# central_sensores.net
KiCad netlist of a schematic drawn in EAGLE
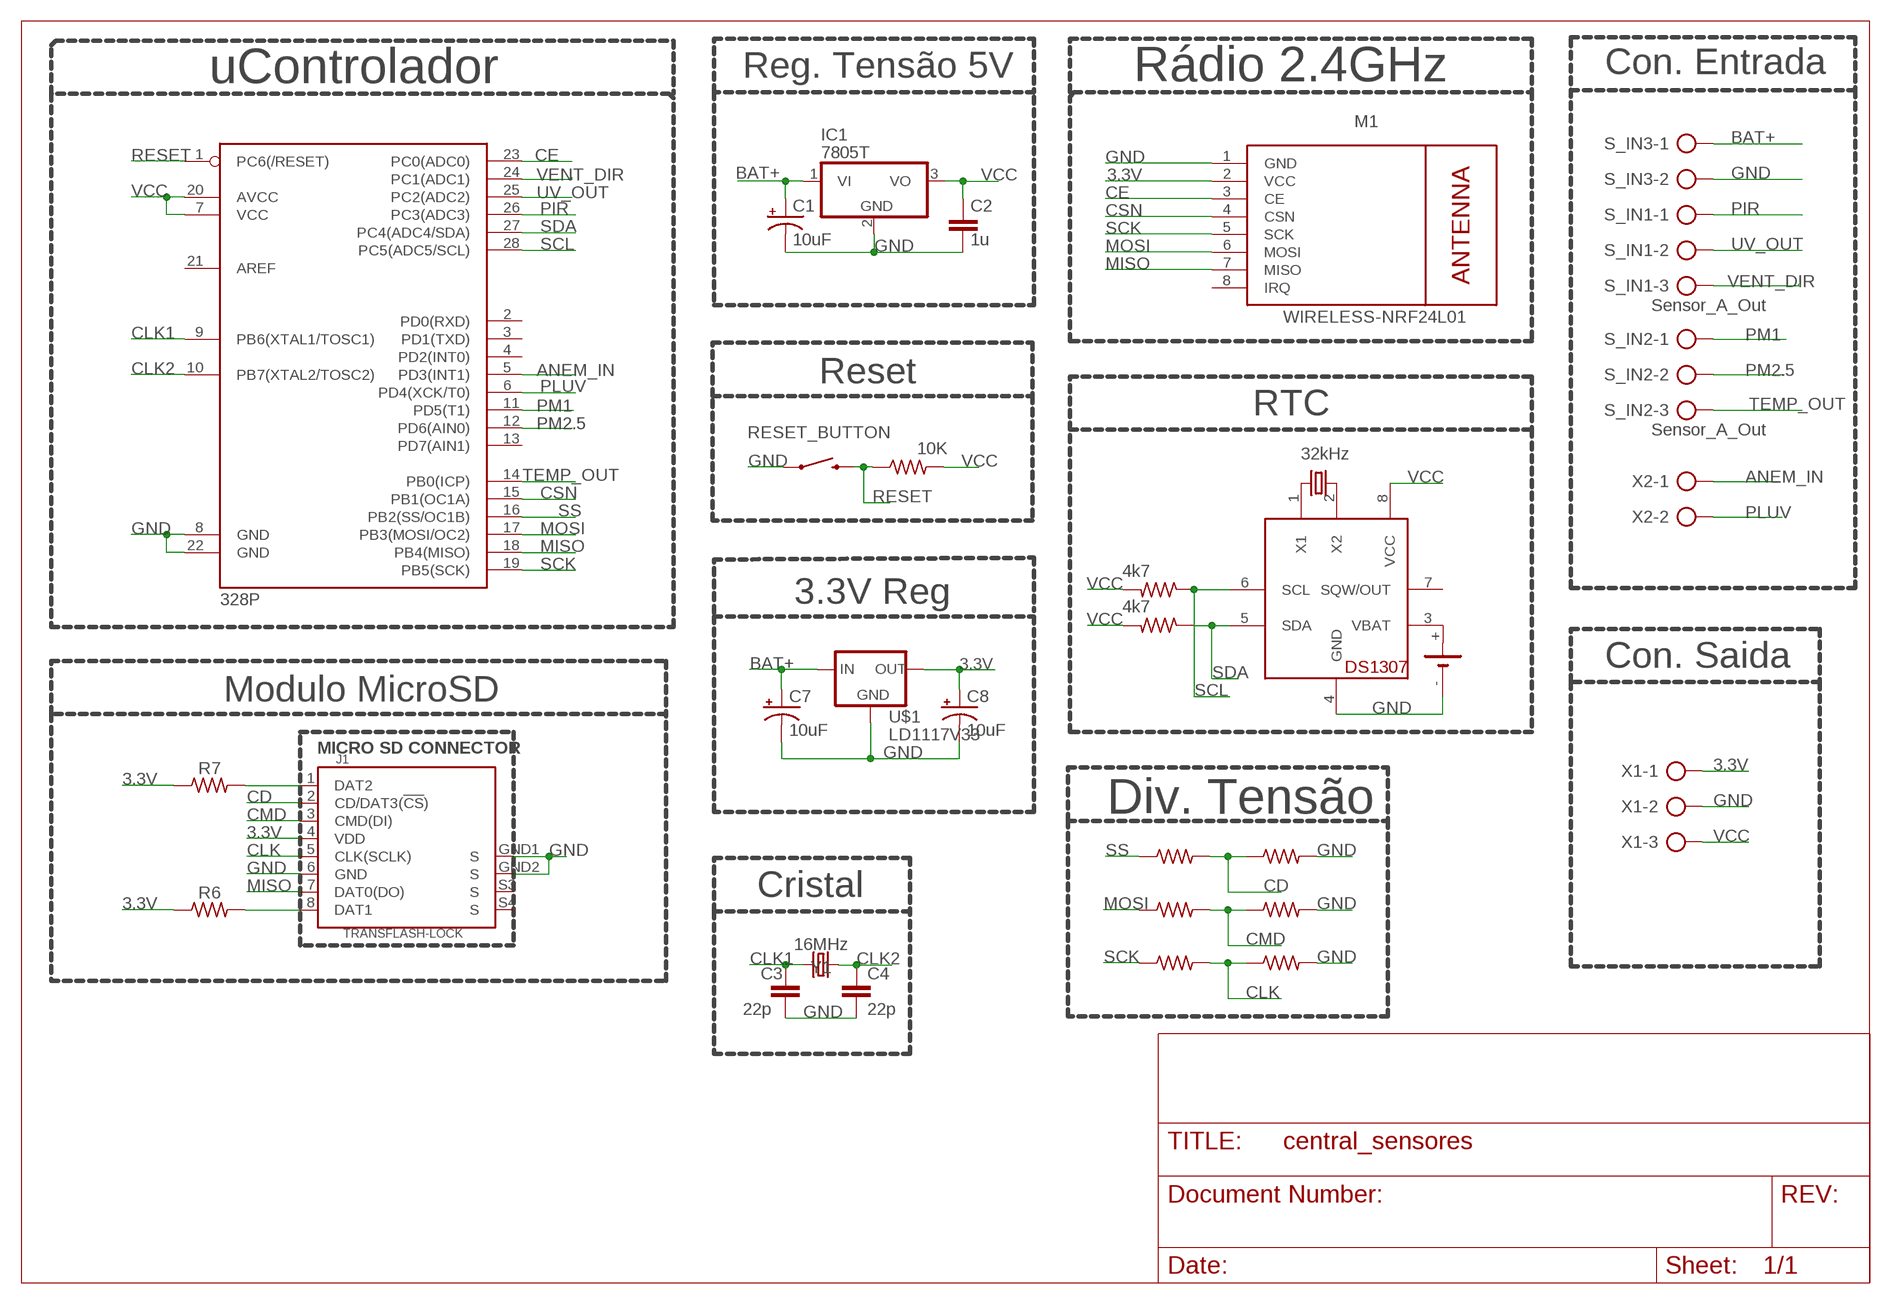
[diagram p0: schematic, sheet 1]

(export (version "E")
  (design (tool "Eeschema 10.0.6"))
  (components
    (comp (ref "C1")
      (value "10uF")
      (footprint "eagle-import:CPOL-RADIAL-2.5MM-5MM")
      (libsource (lib "eagle-import") (part "10UF-POLAR-RADIAL-2.5MM-25V-20%"))
    )
    (comp (ref "C2")
      (value "1u")
      (footprint "eagle-import:C025-024X044")
      (libsource (lib "eagle-import") (part "C-EU025-024X044"))
    )
    (comp (ref "C3")
      (value "22p")
      (footprint "eagle-import:C2.5-3")
      (libsource (lib "eagle-import") (part "C2,5-3"))
    )
    (comp (ref "C4")
      (value "22p")
      (footprint "eagle-import:C2.5-3")
      (libsource (lib "eagle-import") (part "C2,5-3"))
    )
    (comp (ref "C7")
      (value "10uF")
      (footprint "eagle-import:CPOL-RADIAL-2.5MM-5MM")
      (libsource (lib "eagle-import") (part "10UF-POLAR-RADIAL-2.5MM-25V-20%"))
    )
    (comp (ref "C8")
      (value "10uF")
      (footprint "eagle-import:CPOL-RADIAL-2.5MM-5MM")
      (libsource (lib "eagle-import") (part "10UF-POLAR-RADIAL-2.5MM-25V-20%"))
    )
    (comp (ref "G2")
      (value "CH291-1220LF")
      (footprint "eagle-import:CH291-1220LF")
      (libsource (lib "eagle-import") (part "CH291-1220LF"))
    )
    (comp (ref "IC1")
      (value "7805T")
      (footprint "eagle-import:TO220H")
      (libsource (lib "eagle-import") (part "78T05"))
    )
    (comp (ref "IC2")
      (value "DS1307")
      (footprint "eagle-import:DIL08")
      (libsource (lib "eagle-import") (part "DS1307"))
    )
    (comp (ref "J1")
      (value "TRANSFLASH-LOCK")
      (footprint "eagle-import:TRANSFLASH-LOCK-SOCK")
      (libsource (lib "eagle-import") (part "TRANSFLASH-LOCK"))
    )
    (comp (ref "M1")
      (value "WIRELESS-NRF24L01")
      (footprint "eagle-import:WIRELESS-NRF24L01")
      (libsource (lib "eagle-import") (part "WIRELESS-NRF24L01"))
    )
    (comp (ref "R1")
      (value "10K")
      (footprint "eagle-import:0204_7")
      (libsource (lib "eagle-import") (part "R-US_0204/7"))
    )
    (comp (ref "R2")
      (value "R-US_0204/7")
      (footprint "eagle-import:0204_7")
      (libsource (lib "eagle-import") (part "resistor_R-US_0204/7"))
    )
    (comp (ref "R3")
      (value "R-US_0204/7")
      (footprint "eagle-import:0204_7")
      (libsource (lib "eagle-import") (part "resistor_R-US_0204/7"))
    )
    (comp (ref "R4")
      (value "4k7")
      (footprint "eagle-import:0204_7")
      (libsource (lib "eagle-import") (part "R-US_0204/7"))
    )
    (comp (ref "R5")
      (value "4k7")
      (footprint "eagle-import:0204_7")
      (libsource (lib "eagle-import") (part "R-US_0204/7"))
    )
    (comp (ref "R6")
      (value "100k")
      (footprint "eagle-import:0204_7")
      (libsource (lib "eagle-import") (part "resistor_R-US_0204/7"))
    )
    (comp (ref "R7")
      (value "100k")
      (footprint "eagle-import:0204_7")
      (libsource (lib "eagle-import") (part "resistor_R-US_0204/7"))
    )
    (comp (ref "R8")
      (value "R-US_0204/7")
      (footprint "eagle-import:0204_7")
      (libsource (lib "eagle-import") (part "resistor_R-US_0204/7"))
    )
    (comp (ref "R9")
      (value "R-US_0204/7")
      (footprint "eagle-import:0204_7")
      (libsource (lib "eagle-import") (part "resistor_R-US_0204/7"))
    )
    (comp (ref "R10")
      (value "R-US_0204/7")
      (footprint "eagle-import:0204_7")
      (libsource (lib "eagle-import") (part "resistor_R-US_0204/7"))
    )
    (comp (ref "R11")
      (value "R-US_0204/7")
      (footprint "eagle-import:0204_7")
      (libsource (lib "eagle-import") (part "resistor_R-US_0204/7"))
    )
    (comp (ref "RESET_BUTTON")
      (value "MOMENTARY-SWITCH-SPST-PTH-6.0MM")
      (footprint "eagle-import:TACTILE_SWITCH_PTH_6.0MM")
      (libsource (lib "eagle-import") (part "MOMENTARY-SWITCH-SPST-PTH-6.0MM"))
    )
    (comp (ref "S_IN1")
      (value "Sensor_A_Out")
      (footprint "eagle-import:AK500_3-H")
      (libsource (lib "eagle-import") (part "AK500/3-H"))
    )
    (comp (ref "S_IN2")
      (value "Sensor_A_Out")
      (footprint "eagle-import:AK500_3-H")
      (libsource (lib "eagle-import") (part "AK500/3-H"))
    )
    (comp (ref "S_IN3")
      (value "Sensor_A_Out")
      (footprint "eagle-import:AK500_2-H")
      (libsource (lib "eagle-import") (part "AK500/2-H"))
    )
    (comp (ref "U$1")
      (value "LD1117V33")
      (footprint "eagle-import:LD1117V33")
      (libsource (lib "eagle-import") (part "LD1117V33"))
    )
    (comp (ref "U1")
      (value "328P")
      (footprint "eagle-import:DIP28")
      (libsource (lib "eagle-import") (part "ATMEGA328P_PDIP"))
    )
    (comp (ref "X1")
      (value "AK500/3-H")
      (footprint "eagle-import:AK500_3-H")
      (libsource (lib "eagle-import") (part "AK500/3-H"))
    )
    (comp (ref "X2")
      (value "AK500/2-H")
      (footprint "eagle-import:AK500_2-H")
      (libsource (lib "eagle-import") (part "AK500/2-H"))
    )
    (comp (ref "Y1")
      (value "16MHz")
      (footprint "eagle-import:HC49US")
      (libsource (lib "eagle-import") (part "CRYSTAL-16MHZPTH-HC49US"))
    )
    (comp (ref "Y2")
      (value "32kHz")
      (footprint "eagle-import:TC38H")
      (libsource (lib "eagle-import") (part "CRYSTALTC38H"))
    )
  )
  (nets
    (net (code "1") (name "/3.3V") (class "Default")
      (node (ref "C8") (pin "1") (pinfunction "+_1") (pintype "passive"))
      (node (ref "J1") (pin "4") (pinfunction "VDD_4") (pintype "power_in"))
      (node (ref "M1") (pin "2") (pinfunction "VCC_2") (pintype "power_in"))
      (node (ref "R6") (pin "1") (pinfunction "1_1") (pintype "passive"))
      (node (ref "R7") (pin "1") (pinfunction "1_1") (pintype "passive"))
      (node (ref "U$1") (pin "OUT") (pinfunction "OUT_OUT") (pintype "output"))
      (node (ref "X1") (pin "1") (pinfunction "KL_1") (pintype "passive"))
    )
    (net (code "2") (name "/ANEM_IN") (class "Default")
      (node (ref "U1") (pin "5") (pinfunction "PD3(INT1)_5") (pintype "bidirectional"))
      (node (ref "X2") (pin "1") (pinfunction "KL_1") (pintype "passive"))
    )
    (net (code "3") (name "/BAT+") (class "Default")
      (node (ref "C1") (pin "1") (pinfunction "+_1") (pintype "passive"))
      (node (ref "C7") (pin "1") (pinfunction "+_1") (pintype "passive"))
      (node (ref "IC1") (pin "1") (pinfunction "VI_1") (pintype "input"))
      (node (ref "S_IN3") (pin "1") (pinfunction "KL_1") (pintype "passive"))
      (node (ref "U$1") (pin "IN") (pinfunction "IN_IN") (pintype "input"))
    )
    (net (code "4") (name "/CD") (class "Default")
      (node (ref "J1") (pin "2") (pinfunction "CD/DAT3(~{CS})_2") (pintype "bidirectional"))
      (node (ref "R2") (pin "2") (pinfunction "2_2") (pintype "passive"))
      (node (ref "R3") (pin "1") (pinfunction "1_1") (pintype "passive"))
    )
    (net (code "5") (name "/CE") (class "Default")
      (node (ref "M1") (pin "3") (pinfunction "CE_3") (pintype "bidirectional"))
      (node (ref "U1") (pin "23") (pinfunction "PC0(ADC0)_23") (pintype "bidirectional"))
    )
    (net (code "6") (name "/CLK") (class "Default")
      (node (ref "J1") (pin "5") (pinfunction "CLK(SCLK)_5") (pintype "bidirectional"))
      (node (ref "R10") (pin "2") (pinfunction "2_2") (pintype "passive"))
      (node (ref "R11") (pin "1") (pinfunction "1_1") (pintype "passive"))
    )
    (net (code "7") (name "/CLK1") (class "Default")
      (node (ref "C3") (pin "1") (pinfunction "1_1") (pintype "passive"))
      (node (ref "U1") (pin "9") (pinfunction "PB6(XTAL1/TOSC1)_9") (pintype "bidirectional"))
      (node (ref "Y1") (pin "2") (pinfunction "2_2") (pintype "passive"))
    )
    (net (code "8") (name "/CLK2") (class "Default")
      (node (ref "C4") (pin "1") (pinfunction "1_1") (pintype "passive"))
      (node (ref "U1") (pin "10") (pinfunction "PB7(XTAL2/TOSC2)_10") (pintype "bidirectional"))
      (node (ref "Y1") (pin "1") (pinfunction "1_1") (pintype "passive"))
    )
    (net (code "9") (name "/CMD") (class "Default")
      (node (ref "J1") (pin "3") (pinfunction "CMD(DI)_3") (pintype "bidirectional"))
      (node (ref "R8") (pin "2") (pinfunction "2_2") (pintype "passive"))
      (node (ref "R9") (pin "1") (pinfunction "1_1") (pintype "passive"))
    )
    (net (code "10") (name "/CSN") (class "Default")
      (node (ref "M1") (pin "4") (pinfunction "CSN_4") (pintype "bidirectional"))
      (node (ref "U1") (pin "15") (pinfunction "PB1(OC1A)_15") (pintype "bidirectional"))
    )
    (net (code "11") (name "/GND") (class "Default")
      (node (ref "C1") (pin "2") (pinfunction "-_2") (pintype "passive"))
      (node (ref "C2") (pin "2") (pinfunction "2_2") (pintype "passive"))
      (node (ref "C3") (pin "2") (pinfunction "2_2") (pintype "passive"))
      (node (ref "C4") (pin "2") (pinfunction "2_2") (pintype "passive"))
      (node (ref "C7") (pin "2") (pinfunction "-_2") (pintype "passive"))
      (node (ref "C8") (pin "2") (pinfunction "-_2") (pintype "passive"))
      (node (ref "G2") (pin "-") (pinfunction "-_-") (pintype "passive"))
      (node (ref "IC1") (pin "2") (pinfunction "GND_2") (pintype "passive"))
      (node (ref "IC2") (pin "4") (pinfunction "GND_4") (pintype "power_in"))
      (node (ref "J1") (pin "6") (pinfunction "GND_6") (pintype "power_in"))
      (node (ref "J1") (pin "GND1") (pinfunction "S_GND1") (pintype "passive"))
      (node (ref "J1") (pin "GND2") (pinfunction "S_GND2") (pintype "passive"))
      (node (ref "M1") (pin "1") (pinfunction "GND_1") (pintype "power_in"))
      (node (ref "R11") (pin "2") (pinfunction "2_2") (pintype "passive"))
      (node (ref "R3") (pin "2") (pinfunction "2_2") (pintype "passive"))
      (node (ref "R9") (pin "2") (pinfunction "2_2") (pintype "passive"))
      (node (ref "RESET_BUTTON") (pin "1") (pinfunction "1_1") (pintype "passive"))
      (node (ref "S_IN3") (pin "2") (pinfunction "KL_2") (pintype "passive"))
      (node (ref "U$1") (pin "GND") (pinfunction "GND_GND") (pintype "input"))
      (node (ref "U1") (pin "22") (pinfunction "GND_22") (pintype "bidirectional"))
      (node (ref "U1") (pin "8") (pinfunction "GND_8") (pintype "bidirectional"))
      (node (ref "X1") (pin "2") (pinfunction "KL_2") (pintype "passive"))
    )
    (net (code "12") (name "/MISO") (class "Default")
      (node (ref "J1") (pin "7") (pinfunction "DAT0(DO)_7") (pintype "bidirectional"))
      (node (ref "M1") (pin "7") (pinfunction "MISO_7") (pintype "bidirectional"))
      (node (ref "U1") (pin "18") (pinfunction "PB4(MISO)_18") (pintype "bidirectional"))
    )
    (net (code "13") (name "/MOSI") (class "Default")
      (node (ref "M1") (pin "6") (pinfunction "MOSI_6") (pintype "bidirectional"))
      (node (ref "R8") (pin "1") (pinfunction "1_1") (pintype "passive"))
      (node (ref "U1") (pin "17") (pinfunction "PB3(MOSI/OC2)_17") (pintype "bidirectional"))
    )
    (net (code "14") (name "/PIR") (class "Default")
      (node (ref "S_IN1") (pin "1") (pinfunction "KL_1") (pintype "passive"))
      (node (ref "U1") (pin "26") (pinfunction "PC3(ADC3)_26") (pintype "bidirectional"))
    )
    (net (code "15") (name "/PLUV") (class "Default")
      (node (ref "U1") (pin "6") (pinfunction "PD4(XCK/T0)_6") (pintype "bidirectional"))
      (node (ref "X2") (pin "2") (pinfunction "KL_2") (pintype "passive"))
    )
    (net (code "16") (name "/PM1") (class "Default")
      (node (ref "S_IN2") (pin "1") (pinfunction "KL_1") (pintype "passive"))
      (node (ref "U1") (pin "11") (pinfunction "PD5(T1)_11") (pintype "bidirectional"))
    )
    (net (code "17") (name "/PM2.5") (class "Default")
      (node (ref "S_IN2") (pin "2") (pinfunction "KL_2") (pintype "passive"))
      (node (ref "U1") (pin "12") (pinfunction "PD6(AIN0)_12") (pintype "bidirectional"))
    )
    (net (code "18") (name "/RESET") (class "Default")
      (node (ref "R1") (pin "1") (pinfunction "1_1") (pintype "passive"))
      (node (ref "RESET_BUTTON") (pin "3") (pinfunction "2_3") (pintype "passive"))
      (node (ref "U1") (pin "1") (pinfunction "PC6(/RESET)_1") (pintype "bidirectional"))
    )
    (net (code "19") (name "/SCK") (class "Default")
      (node (ref "M1") (pin "5") (pinfunction "SCK_5") (pintype "bidirectional"))
      (node (ref "R10") (pin "1") (pinfunction "1_1") (pintype "passive"))
      (node (ref "U1") (pin "19") (pinfunction "PB5(SCK)_19") (pintype "bidirectional"))
    )
    (net (code "20") (name "/SCL") (class "Default")
      (node (ref "IC2") (pin "6") (pinfunction "SCL_6") (pintype "bidirectional"))
      (node (ref "R4") (pin "1") (pinfunction "1_1") (pintype "passive"))
      (node (ref "U1") (pin "28") (pinfunction "PC5(ADC5/SCL)_28") (pintype "bidirectional"))
    )
    (net (code "21") (name "/SDA") (class "Default")
      (node (ref "IC2") (pin "5") (pinfunction "SDA_5") (pintype "bidirectional"))
      (node (ref "R5") (pin "1") (pinfunction "1_1") (pintype "passive"))
      (node (ref "U1") (pin "27") (pinfunction "PC4(ADC4/SDA)_27") (pintype "bidirectional"))
    )
    (net (code "22") (name "/SS") (class "Default")
      (node (ref "R2") (pin "1") (pinfunction "1_1") (pintype "passive"))
      (node (ref "U1") (pin "16") (pinfunction "PB2(SS/OC1B)_16") (pintype "bidirectional"))
    )
    (net (code "23") (name "/TEMP_OUT") (class "Default")
      (node (ref "S_IN2") (pin "3") (pinfunction "KL_3") (pintype "passive"))
      (node (ref "U1") (pin "14") (pinfunction "PB0(ICP)_14") (pintype "bidirectional"))
    )
    (net (code "24") (name "/UV_OUT") (class "Default")
      (node (ref "S_IN1") (pin "2") (pinfunction "KL_2") (pintype "passive"))
      (node (ref "U1") (pin "25") (pinfunction "PC2(ADC2)_25") (pintype "bidirectional"))
    )
    (net (code "25") (name "/VCC") (class "Default")
      (node (ref "C2") (pin "1") (pinfunction "1_1") (pintype "passive"))
      (node (ref "IC1") (pin "3") (pinfunction "VO_3") (pintype "passive"))
      (node (ref "IC2") (pin "8") (pinfunction "VCC_8") (pintype "power_in"))
      (node (ref "R1") (pin "2") (pinfunction "2_2") (pintype "passive"))
      (node (ref "R4") (pin "2") (pinfunction "2_2") (pintype "passive"))
      (node (ref "R5") (pin "2") (pinfunction "2_2") (pintype "passive"))
      (node (ref "U1") (pin "20") (pinfunction "AVCC_20") (pintype "bidirectional"))
      (node (ref "U1") (pin "7") (pinfunction "VCC_7") (pintype "bidirectional"))
      (node (ref "X1") (pin "3") (pinfunction "KL_3") (pintype "passive"))
    )
    (net (code "26") (name "/VENT_DIR") (class "Default")
      (node (ref "S_IN1") (pin "3") (pinfunction "KL_3") (pintype "passive"))
      (node (ref "U1") (pin "24") (pinfunction "PC1(ADC1)_24") (pintype "bidirectional"))
    )
    (net (code "27") (name "Net-(IC2-VBAT)") (class "Default")
      (node (ref "G2") (pin "+") (pinfunction "+_+") (pintype "passive"))
      (node (ref "IC2") (pin "3") (pinfunction "VBAT_3") (pintype "power_in"))
    )
    (net (code "28") (name "Net-(IC2-X1)") (class "Default")
      (node (ref "IC2") (pin "1") (pinfunction "X1_1") (pintype "passive"))
      (node (ref "Y2") (pin "1") (pinfunction "1_1") (pintype "passive"))
    )
    (net (code "29") (name "Net-(IC2-X2)") (class "Default")
      (node (ref "IC2") (pin "2") (pinfunction "X2_2") (pintype "passive"))
      (node (ref "Y2") (pin "2") (pinfunction "2_2") (pintype "passive"))
    )
    (net (code "30") (name "Net-(J1-DAT1)") (class "Default")
      (node (ref "J1") (pin "8") (pinfunction "DAT1_8") (pintype "bidirectional"))
      (node (ref "R6") (pin "2") (pinfunction "2_2") (pintype "passive"))
    )
    (net (code "31") (name "Net-(J1-DAT2)") (class "Default")
      (node (ref "J1") (pin "1") (pinfunction "DAT2_1") (pintype "bidirectional"))
      (node (ref "R7") (pin "2") (pinfunction "2_2") (pintype "passive"))
    )
    (net (code "32") (name "unconnected-(IC2-SQW{slash}OUT-Pad7)") (class "Default")
      (node (ref "IC2") (pin "7") (pinfunction "SQW/OUT_7") (pintype "bidirectional"))
    )
    (net (code "33") (name "unconnected-(J1-S-PadS3)") (class "Default")
      (node (ref "J1") (pin "S3") (pinfunction "S_S3") (pintype "passive"))
    )
    (net (code "34") (name "unconnected-(J1-S-PadS4)") (class "Default")
      (node (ref "J1") (pin "S4") (pinfunction "S_S4") (pintype "passive"))
    )
    (net (code "35") (name "unconnected-(M1-IRQ-Pad8)") (class "Default")
      (node (ref "M1") (pin "8") (pinfunction "IRQ_8") (pintype "bidirectional"))
    )
    (net (code "36") (name "unconnected-(U1-AREF-Pad21)") (class "Default")
      (node (ref "U1") (pin "21") (pinfunction "AREF_21") (pintype "bidirectional"))
    )
    (net (code "37") (name "unconnected-(U1-PD0(RXD)-Pad2)") (class "Default")
      (node (ref "U1") (pin "2") (pinfunction "PD0(RXD)_2") (pintype "bidirectional"))
    )
    (net (code "38") (name "unconnected-(U1-PD1(TXD)-Pad3)") (class "Default")
      (node (ref "U1") (pin "3") (pinfunction "PD1(TXD)_3") (pintype "bidirectional"))
    )
    (net (code "39") (name "unconnected-(U1-PD2(INT0)-Pad4)") (class "Default")
      (node (ref "U1") (pin "4") (pinfunction "PD2(INT0)_4") (pintype "bidirectional"))
    )
    (net (code "40") (name "unconnected-(U1-PD7(AIN1)-Pad13)") (class "Default")
      (node (ref "U1") (pin "13") (pinfunction "PD7(AIN1)_13") (pintype "bidirectional"))
    )
  )
)
